# USB_to_USART.net
KiCad netlist of a schematic drawn in EAGLE
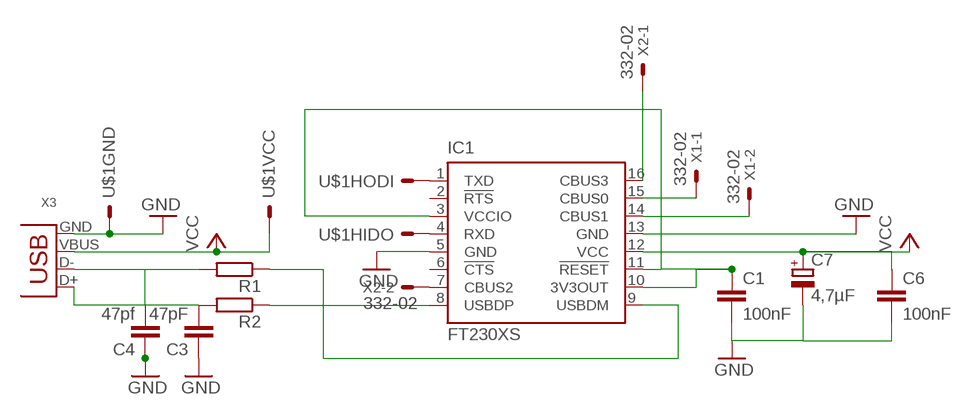
[diagram p0: schematic, sheet 1]

(export (version "E")
  (design (tool "Eeschema 10.0.6"))
  (components
    (comp (ref "C1")
      (value "100nF")
      (footprint "eagle-import:C025-030X050")
      (libsource (lib "eagle-import") (part "C-EU025-030X050"))
    )
    (comp (ref "C3")
      (value "47pF")
      (footprint "eagle-import:C025-030X050")
      (libsource (lib "eagle-import") (part "C-EU025-030X050"))
    )
    (comp (ref "C4")
      (value "47pf")
      (footprint "eagle-import:C025-030X050")
      (libsource (lib "eagle-import") (part "C-EU025-030X050"))
    )
    (comp (ref "C6")
      (value "100nF")
      (footprint "eagle-import:C025-030X050")
      (libsource (lib "eagle-import") (part "C-EU025-030X050"))
    )
    (comp (ref "C7")
      (value "4,7µF")
      (footprint "eagle-import:B45181B")
      (libsource (lib "eagle-import") (part "CPOL-EUB45181B"))
    )
    (comp (ref "IC1")
      (value "FT230XS")
      (footprint "eagle-import:SSOP16")
      (libsource (lib "eagle-import") (part "FT230XS"))
    )
    (comp (ref "R1")
      (value "R-EU_0204/7")
      (footprint "eagle-import:0204_7")
      (libsource (lib "eagle-import") (part "R-EU_0204/7"))
    )
    (comp (ref "R2")
      (value "R-EU_0204/7")
      (footprint "eagle-import:0204_7")
      (libsource (lib "eagle-import") (part "R-EU_0204/7"))
    )
    (comp (ref "U$1")
      (value "UARTUSB")
      (footprint "eagle-import:PN61729")
      (libsource (lib "eagle-import") (part "UARTUSB"))
    )
    (comp (ref "X1")
      (value "332-02")
      (footprint "eagle-import:332-02")
      (libsource (lib "eagle-import") (part "332-02"))
    )
    (comp (ref "X2")
      (value "332-02")
      (footprint "eagle-import:332-02")
      (libsource (lib "eagle-import") (part "332-02"))
    )
    (comp (ref "X3")
      (value "USB-B-H")
      (footprint "eagle-import:USB-B-H")
      (libsource (lib "eagle-import") (part "USB-B-H"))
    )
  )
  (nets
    (net (code "1") (name "GND") (class "Default")
      (node (ref "C1") (pin "2") (pinfunction "2_2") (pintype "passive"))
      (node (ref "C3") (pin "1") (pinfunction "1_1") (pintype "passive"))
      (node (ref "C4") (pin "1") (pinfunction "1_1") (pintype "passive"))
      (node (ref "C6") (pin "2") (pinfunction "2_2") (pintype "passive"))
      (node (ref "C7") (pin "-") (pinfunction "-_-") (pintype "passive"))
      (node (ref "IC1") (pin "13") (pinfunction "GND_13") (pintype "power_in"))
      (node (ref "IC1") (pin "5") (pinfunction "GND_5") (pintype "power_in"))
      (node (ref "U$1") (pin "4") (pinfunction "S_4") (pintype "passive"))
      (node (ref "X3") (pin "GND") (pinfunction "GND_GND") (pintype "bidirectional"))
    )
    (net (code "2") (name "Net-(C3-Pad2)") (class "Default")
      (node (ref "C3") (pin "2") (pinfunction "2_2") (pintype "passive"))
      (node (ref "R2") (pin "2") (pinfunction "2_2") (pintype "passive"))
      (node (ref "X3") (pin "D+") (pinfunction "D+_D+") (pintype "bidirectional"))
    )
    (net (code "3") (name "Net-(C4-Pad2)") (class "Default")
      (node (ref "C4") (pin "2") (pinfunction "2_2") (pintype "passive"))
      (node (ref "R1") (pin "2") (pinfunction "2_2") (pintype "passive"))
      (node (ref "X3") (pin "D-") (pinfunction "D-_D-") (pintype "bidirectional"))
    )
    (net (code "4") (name "Net-(IC1-3V3OUT)") (class "Default")
      (node (ref "C1") (pin "1") (pinfunction "1_1") (pintype "passive"))
      (node (ref "IC1") (pin "10") (pinfunction "3V3OUT_10") (pintype "output"))
      (node (ref "IC1") (pin "11") (pinfunction "~{RESET}_11") (pintype "input"))
      (node (ref "IC1") (pin "3") (pinfunction "VCCIO_3") (pintype "power_in"))
    )
    (net (code "5") (name "Net-(IC1-CBUS0)") (class "Default")
      (node (ref "IC1") (pin "15") (pinfunction "CBUS0_15") (pintype "bidirectional"))
      (node (ref "X1") (pin "1") (pinfunction "S_1") (pintype "passive"))
    )
    (net (code "6") (name "Net-(IC1-CBUS1)") (class "Default")
      (node (ref "IC1") (pin "14") (pinfunction "CBUS1_14") (pintype "bidirectional"))
      (node (ref "X1") (pin "2") (pinfunction "S_2") (pintype "passive"))
    )
    (net (code "7") (name "Net-(IC1-CBUS2)") (class "Default")
      (node (ref "IC1") (pin "7") (pinfunction "CBUS2_7") (pintype "bidirectional"))
      (node (ref "X2") (pin "2") (pinfunction "S_2") (pintype "passive"))
    )
    (net (code "8") (name "Net-(IC1-CBUS3)") (class "Default")
      (node (ref "IC1") (pin "16") (pinfunction "CBUS3_16") (pintype "bidirectional"))
      (node (ref "X2") (pin "1") (pinfunction "S_1") (pintype "passive"))
    )
    (net (code "9") (name "Net-(IC1-RXD)") (class "Default")
      (node (ref "IC1") (pin "4") (pinfunction "RXD_4") (pintype "input"))
      (node (ref "U$1") (pin "2") (pinfunction "S_2") (pintype "passive"))
    )
    (net (code "10") (name "Net-(IC1-TXD)") (class "Default")
      (node (ref "IC1") (pin "1") (pinfunction "TXD_1") (pintype "output"))
      (node (ref "U$1") (pin "3") (pinfunction "S_3") (pintype "passive"))
    )
    (net (code "11") (name "Net-(IC1-USBDM)") (class "Default")
      (node (ref "IC1") (pin "9") (pinfunction "USBDM_9") (pintype "input"))
      (node (ref "R1") (pin "1") (pinfunction "1_1") (pintype "passive"))
    )
    (net (code "12") (name "Net-(IC1-USBDP)") (class "Default")
      (node (ref "IC1") (pin "8") (pinfunction "USBDP_8") (pintype "input"))
      (node (ref "R2") (pin "1") (pinfunction "1_1") (pintype "passive"))
    )
    (net (code "13") (name "VCC") (class "Default")
      (node (ref "C6") (pin "1") (pinfunction "1_1") (pintype "passive"))
      (node (ref "C7") (pin "+") (pinfunction "+_+") (pintype "passive"))
      (node (ref "IC1") (pin "12") (pinfunction "VCC_12") (pintype "power_in"))
      (node (ref "U$1") (pin "1") (pinfunction "S_1") (pintype "passive"))
      (node (ref "X3") (pin "VBUS") (pinfunction "VBUS_VBUS") (pintype "bidirectional"))
    )
    (net (code "14") (name "unconnected-(IC1-~{CTS}-Pad6)") (class "Default")
      (node (ref "IC1") (pin "6") (pinfunction "~{CTS}_6") (pintype "input"))
    )
    (net (code "15") (name "unconnected-(IC1-~{RTS}-Pad2)") (class "Default")
      (node (ref "IC1") (pin "2") (pinfunction "~{RTS}_2") (pintype "output"))
    )
  )
)
